# 2uprava3.net
KiCad netlist of a schematic drawn in EAGLE
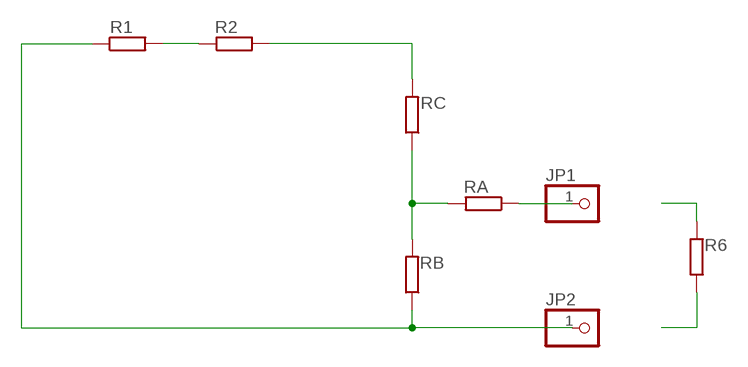
[diagram p0: schematic, sheet 1]

(export (version "E")
  (design (tool "Eeschema 10.0.6"))
  (components
    (comp (ref "JP1")
      (value "PINHD-1X1")
      (footprint "eagle-import:1X01")
      (libsource (lib "eagle-import") (part "PINHD-1X1"))
    )
    (comp (ref "JP2")
      (value "PINHD-1X1")
      (footprint "eagle-import:1X01")
      (libsource (lib "eagle-import") (part "PINHD-1X1"))
    )
    (comp (ref "R1")
      (value "50R")
      (footprint "eagle-import:0204_7")
      (libsource (lib "eagle-import") (part "R-EU_0204/7"))
    )
    (comp (ref "R2")
      (value "50R")
      (footprint "eagle-import:0204_7")
      (libsource (lib "eagle-import") (part "R-EU_0204/7"))
    )
    (comp (ref "R6")
      (value "200R")
      (footprint "eagle-import:0204_7")
      (libsource (lib "eagle-import") (part "R-EU_0204/7"))
    )
    (comp (ref "RA")
      (value "570R")
      (footprint "eagle-import:0204_7")
      (libsource (lib "eagle-import") (part "R-EU_0204/7"))
    )
    (comp (ref "RB")
      (value "610R")
      (footprint "eagle-import:0204_7")
      (libsource (lib "eagle-import") (part "R-EU_0204/7"))
    )
    (comp (ref "RC")
      (value "220R")
      (footprint "eagle-import:0204_7")
      (libsource (lib "eagle-import") (part "R-EU_0204/7"))
    )
  )
  (nets
    (net (code "1") (name "Net-(JP1-Pad1)") (class "Default")
      (node (ref "JP1") (pin "1") (pinfunction "1_1") (pintype "passive"))
      (node (ref "RA") (pin "1") (pinfunction "1_1") (pintype "passive"))
    )
    (net (code "2") (name "Net-(JP2-Pad1)") (class "Default")
      (node (ref "JP2") (pin "1") (pinfunction "1_1") (pintype "passive"))
      (node (ref "R1") (pin "1") (pinfunction "1_1") (pintype "passive"))
      (node (ref "RB") (pin "1") (pinfunction "1_1") (pintype "passive"))
    )
    (net (code "3") (name "Net-(R1-Pad2)") (class "Default")
      (node (ref "R1") (pin "2") (pinfunction "2_2") (pintype "passive"))
      (node (ref "R2") (pin "1") (pinfunction "1_1") (pintype "passive"))
    )
    (net (code "4") (name "Net-(R2-Pad2)") (class "Default")
      (node (ref "R2") (pin "2") (pinfunction "2_2") (pintype "passive"))
      (node (ref "RC") (pin "2") (pinfunction "2_2") (pintype "passive"))
    )
    (net (code "5") (name "Net-(RA-Pad2)") (class "Default")
      (node (ref "RA") (pin "2") (pinfunction "2_2") (pintype "passive"))
      (node (ref "RB") (pin "2") (pinfunction "2_2") (pintype "passive"))
      (node (ref "RC") (pin "1") (pinfunction "1_1") (pintype "passive"))
    )
    (net (code "6") (name "unconnected-(R6-Pad1)") (class "Default")
      (node (ref "R6") (pin "1") (pinfunction "1_1") (pintype "passive"))
    )
    (net (code "7") (name "unconnected-(R6-Pad2)") (class "Default")
      (node (ref "R6") (pin "2") (pinfunction "2_2") (pintype "passive"))
    )
  )
)
